# cpu_board.net
KiCad netlist of a schematic drawn in Altium Designer
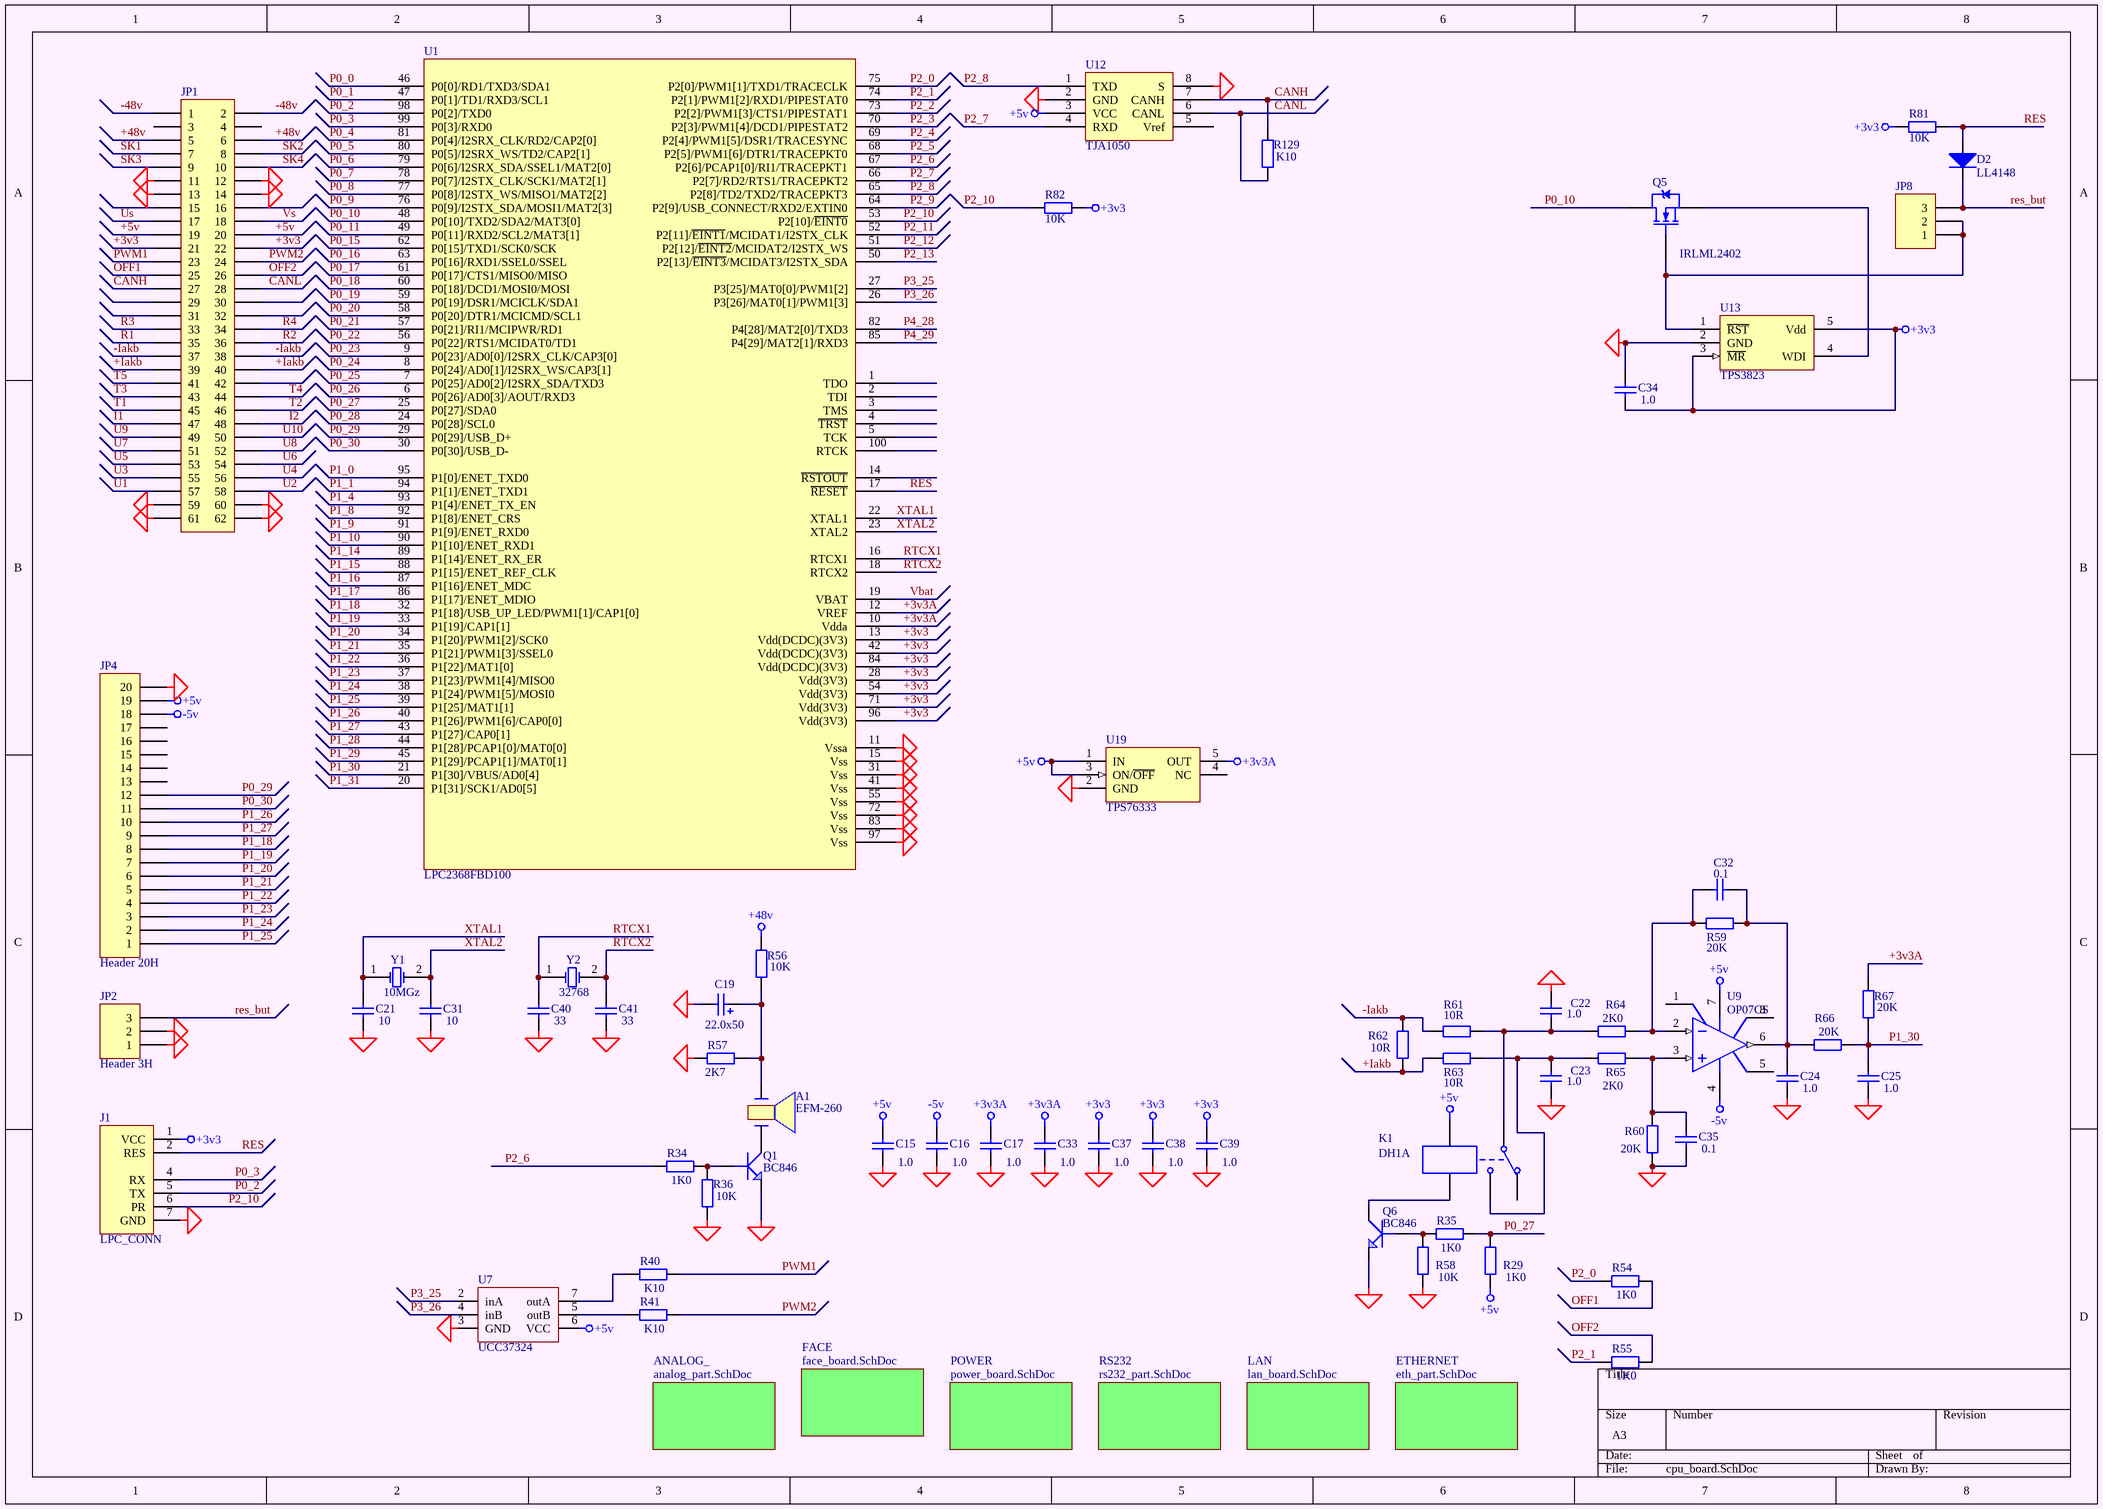
[diagram p0: cpu_board.SchDoc]

(export (version "E")
  (design (tool "Eeschema 10.0.6"))
  (components
    (comp (ref "A1") (value "EFM-260") (footprint "Pjezo15") (libsource (lib "PAL") (part "PJEZ0")))
    (comp (ref "C15")
      (value "1.0")
      (footprint "C3216-1206")
      (description "Capacitor (Semiconductor SIM Model)")
      (fields (field (name "MANUFACTURER") "Generic Components") (field (name "PUBLISHER") "Altium Limited"))
      (libsource (lib "Miscellaneous Devices") (part "Cap Semi"))
    )
    (comp (ref "C16")
      (value "1.0")
      (footprint "C3216-1206")
      (description "Capacitor (Semiconductor SIM Model)")
      (fields (field (name "MANUFACTURER") "Generic Components") (field (name "PUBLISHER") "Altium Limited"))
      (libsource (lib "Miscellaneous Devices") (part "Cap Semi"))
    )
    (comp (ref "C17")
      (value "1.0")
      (footprint "_1206")
      (description "Capacitor (Semiconductor SIM Model)")
      (fields (field (name "MANUFACTURER") "Generic Components") (field (name "PUBLISHER") "Altium Limited"))
      (libsource (lib "Miscellaneous Devices") (part "Cap Semi"))
    )
    (comp (ref "C19")
      (value "22.0x50")
      (footprint "el3")
      (description "Polarized Capacitor (Radial)")
      (fields (field (name "MANUFACTURER") "Generic Components") (field (name "PUBLISHER") "Altium Limited"))
      (libsource (lib "PAL") (part "Cap Pol1"))
    )
    (comp (ref "C21")
      (value "10")
      (footprint "_1206")
      (description "Capacitor (Semiconductor SIM Model)")
      (fields (field (name "MANUFACTURER") "Generic Components") (field (name "PUBLISHER") "Altium Limited"))
      (libsource (lib "Miscellaneous Devices") (part "Cap Semi"))
    )
    (comp (ref "C22")
      (value "1.0")
      (footprint "_1206")
      (description "Capacitor (Semiconductor SIM Model)")
      (fields (field (name "MANUFACTURER") "Generic Components") (field (name "PUBLISHER") "Altium Limited"))
      (libsource (lib "Miscellaneous Devices") (part "Cap Semi"))
    )
    (comp (ref "C23")
      (value "1.0")
      (footprint "_1206")
      (description "Capacitor (Semiconductor SIM Model)")
      (fields (field (name "MANUFACTURER") "Generic Components") (field (name "PUBLISHER") "Altium Limited"))
      (libsource (lib "Miscellaneous Devices") (part "Cap Semi"))
    )
    (comp (ref "C24")
      (value "1.0")
      (footprint "_1206")
      (description "Capacitor (Semiconductor SIM Model)")
      (fields (field (name "MANUFACTURER") "Generic Components") (field (name "PUBLISHER") "Altium Limited"))
      (libsource (lib "Miscellaneous Devices") (part "Cap Semi"))
    )
    (comp (ref "C25")
      (value "1.0")
      (footprint "_1206")
      (description "Capacitor (Semiconductor SIM Model)")
      (fields (field (name "MANUFACTURER") "Generic Components") (field (name "PUBLISHER") "Altium Limited"))
      (libsource (lib "Miscellaneous Devices") (part "Cap Semi"))
    )
    (comp (ref "C31")
      (value "10")
      (footprint "_1206")
      (description "Capacitor (Semiconductor SIM Model)")
      (fields (field (name "MANUFACTURER") "Generic Components") (field (name "PUBLISHER") "Altium Limited"))
      (libsource (lib "Miscellaneous Devices") (part "Cap Semi"))
    )
    (comp (ref "C32")
      (value "0.1")
      (footprint "_1206")
      (description "Capacitor (Semiconductor SIM Model)")
      (fields (field (name "MANUFACTURER") "Generic Components") (field (name "PUBLISHER") "Altium Limited"))
      (libsource (lib "Miscellaneous Devices") (part "Cap Semi"))
    )
    (comp (ref "C33")
      (value "1.0")
      (footprint "_1206")
      (description "Capacitor (Semiconductor SIM Model)")
      (fields (field (name "MANUFACTURER") "Generic Components") (field (name "PUBLISHER") "Altium Limited"))
      (libsource (lib "Miscellaneous Devices") (part "Cap Semi"))
    )
    (comp (ref "C34")
      (value "1.0")
      (footprint "_1206")
      (description "Capacitor")
      (fields (field (name "MANUFACTURER") "Generic Components") (field (name "PUBLISHER") "Altium Limited"))
      (libsource (lib "Miscellaneous Devices") (part "Cap Semi"))
    )
    (comp (ref "C35")
      (value "0.1")
      (footprint "_1206")
      (description "Capacitor (Semiconductor SIM Model)")
      (fields (field (name "MANUFACTURER") "Generic Components") (field (name "PUBLISHER") "Altium Limited"))
      (libsource (lib "Miscellaneous Devices") (part "Cap Semi"))
    )
    (comp (ref "C37")
      (value "1.0")
      (footprint "_1206")
      (description "Capacitor (Semiconductor SIM Model)")
      (fields (field (name "MANUFACTURER") "Generic Components") (field (name "PUBLISHER") "Altium Limited"))
      (libsource (lib "Miscellaneous Devices") (part "Cap Semi"))
    )
    (comp (ref "C38")
      (value "1.0")
      (footprint "_1206")
      (description "Capacitor (Semiconductor SIM Model)")
      (fields (field (name "MANUFACTURER") "Generic Components") (field (name "PUBLISHER") "Altium Limited"))
      (libsource (lib "Miscellaneous Devices") (part "Cap Semi"))
    )
    (comp (ref "C39")
      (value "1.0")
      (footprint "_1206")
      (description "Capacitor (Semiconductor SIM Model)")
      (fields (field (name "MANUFACTURER") "Generic Components") (field (name "PUBLISHER") "Altium Limited"))
      (libsource (lib "Miscellaneous Devices") (part "Cap Semi"))
    )
    (comp (ref "C40")
      (value "33")
      (footprint "_1206")
      (description "Capacitor (Semiconductor SIM Model)")
      (fields (field (name "MANUFACTURER") "Generic Components") (field (name "PUBLISHER") "Altium Limited"))
      (libsource (lib "Miscellaneous Devices") (part "Cap Semi"))
    )
    (comp (ref "C41")
      (value "33")
      (footprint "_1206")
      (description "Capacitor (Semiconductor SIM Model)")
      (fields (field (name "MANUFACTURER") "Generic Components") (field (name "PUBLISHER") "Altium Limited"))
      (libsource (lib "Miscellaneous Devices") (part "Cap Semi"))
    )
    (comp (ref "D2")
      (value "LL4148")
      (footprint "_1206d")
      (description "Default Diode")
      (fields (field (name "MANUFACTURER") "Generic Components") (field (name "PUBLISHER") "Altium Limited"))
      (libsource (lib "PAL") (part "Diode"))
    )
    (comp (ref "J1") (value "LPC_CONN") (footprint "HDR1X7") (libsource (lib "PAL") (part "LPC_CONN")))
    (comp (ref "JP1")
      (value "~")
      (footprint "HDR2X30")
      (description "Header, 30-Pin, Dual row")
      (fields (field (name "MANUFACTURER") "Generic Components") (field (name "PUBLISHER") "Altium Limited"))
      (libsource (lib "UKU205") (part "Header 31X2"))
    )
    (comp (ref "JP2")
      (value "Header 3H")
      (footprint "HDR1X3H")
      (description "Header, 3-Pin,  Right Angle")
      (fields (field (name "MANUFACTURER") "Generic Components") (field (name "PUBLISHER") "Altium Limited"))
      (libsource (lib "Miscellaneous Connectors") (part "Header 3H"))
    )
    (comp (ref "JP4")
      (value "Header 20H")
      (footprint "HDR1X20H")
      (description "Header, 20-Pin,  Right Angle")
      (fields (field (name "MANUFACTURER") "Generic Components") (field (name "PUBLISHER") "Altium Limited"))
      (libsource (lib "Miscellaneous Connectors") (part "Header 20H"))
    )
    (comp (ref "JP8")
      (value "PLS-3")
      (footprint "HDR1X3")
      (description "Header, 3-Pin")
      (fields (field (name "MANUFACTURER") "Generic Components") (field (name "PUBLISHER") "Altium Limited"))
      (libsource (lib "Miscellaneous Connectors") (part "Header 3"))
    )
    (comp (ref "K1")
      (value "DH1A")
      (footprint "kuan")
      (description "Single-Pole Dual-Throw Relay")
      (fields (field (name "MANUFACTURER") "Generic Components") (field (name "PUBLISHER") "Altium Limited"))
      (libsource (lib "PAL") (part "BS115"))
    )
    (comp (ref "Q1") (value "BC846") (footprint "SO-G3") (libsource (lib "MAIN") (part "GT122")))
    (comp (ref "Q5")
      (value "IRLML2402")
      (footprint "SO-G3")
      (description "HEXFET Power MOSFET")
      (fields
        (field (name "MANUFACTURER") "International Rectifier")
        (field (name "PUBLISHER") "Altium Limited")
      )
      (libsource (lib "IR Discrete MOSFET") (part "IRLML2402"))
    )
    (comp (ref "Q6") (value "BC846") (footprint "SO-G3") (libsource (lib "MAIN") (part "GT122")))
    (comp (ref "R29")
      (value "1K0")
      (footprint "_1206")
      (description "Resistor")
      (fields (field (name "MANUFACTURER") "Generic Components") (field (name "PUBLISHER") "Altium Limited"))
      (libsource (lib "") (part "Res2_1"))
    )
    (comp (ref "R34")
      (value "1K0")
      (footprint "_1206")
      (description "Resistor")
      (fields (field (name "MANUFACTURER") "Generic Components") (field (name "PUBLISHER") "Altium Limited"))
      (libsource (lib "") (part "Res2_1"))
    )
    (comp (ref "R35")
      (value "1K0")
      (footprint "_1206")
      (description "Resistor")
      (fields (field (name "MANUFACTURER") "Generic Components") (field (name "PUBLISHER") "Altium Limited"))
      (libsource (lib "") (part "Res2_3"))
    )
    (comp (ref "R36")
      (value "10K")
      (footprint "_1206")
      (description "Resistor")
      (fields (field (name "MANUFACTURER") "Generic Components") (field (name "PUBLISHER") "Altium Limited"))
      (libsource (lib "") (part "Res2_2"))
    )
    (comp (ref "R40")
      (value "K10")
      (footprint "_1206")
      (description "Resistor")
      (fields (field (name "MANUFACTURER") "Generic Components") (field (name "PUBLISHER") "Altium Limited"))
      (libsource (lib "Miscellaneous Devices") (part "Res2"))
    )
    (comp (ref "R41")
      (value "K10")
      (footprint "_1206")
      (description "Resistor")
      (fields (field (name "MANUFACTURER") "Generic Components") (field (name "PUBLISHER") "Altium Limited"))
      (libsource (lib "Miscellaneous Devices") (part "Res2"))
    )
    (comp (ref "R54")
      (value "1K0")
      (footprint "_1206")
      (description "Resistor")
      (fields (field (name "MANUFACTURER") "Generic Components") (field (name "PUBLISHER") "Altium Limited"))
      (libsource (lib "") (part "Res2_1"))
    )
    (comp (ref "R55")
      (value "1K0")
      (footprint "_1206")
      (description "Resistor")
      (fields (field (name "MANUFACTURER") "Generic Components") (field (name "PUBLISHER") "Altium Limited"))
      (libsource (lib "") (part "Res2_1"))
    )
    (comp (ref "R56")
      (value "10K")
      (footprint "_1206")
      (description "Resistor")
      (fields (field (name "MANUFACTURER") "Generic Components") (field (name "PUBLISHER") "Altium Limited"))
      (libsource (lib "") (part "Res2_2"))
    )
    (comp (ref "R57")
      (value "2K7")
      (footprint "_1206")
      (description "Resistor")
      (fields (field (name "MANUFACTURER") "Generic Components") (field (name "PUBLISHER") "Altium Limited"))
      (libsource (lib "") (part "Res2_1"))
    )
    (comp (ref "R58")
      (value "10K")
      (footprint "_1206")
      (description "Resistor")
      (fields (field (name "MANUFACTURER") "Generic Components") (field (name "PUBLISHER") "Altium Limited"))
      (libsource (lib "") (part "Res2_1"))
    )
    (comp (ref "R59")
      (value "20K")
      (footprint "_1206")
      (description "Resistor")
      (fields (field (name "MANUFACTURER") "Generic Components") (field (name "PUBLISHER") "Altium Limited"))
      (libsource (lib "Miscellaneous Devices") (part "Res2"))
    )
    (comp (ref "R60")
      (value "20K")
      (footprint "_1206")
      (description "Resistor")
      (fields (field (name "MANUFACTURER") "Generic Components") (field (name "PUBLISHER") "Altium Limited"))
      (libsource (lib "") (part "Res2_2"))
    )
    (comp (ref "R61")
      (value "10R")
      (footprint "_1206")
      (description "Resistor")
      (fields (field (name "MANUFACTURER") "Generic Components") (field (name "PUBLISHER") "Altium Limited"))
      (libsource (lib "Miscellaneous Devices") (part "Res2"))
    )
    (comp (ref "R62")
      (value "10R")
      (footprint "_1206")
      (description "Resistor")
      (fields (field (name "MANUFACTURER") "Generic Components") (field (name "PUBLISHER") "Altium Limited"))
      (libsource (lib "") (part "Res2_2"))
    )
    (comp (ref "R63")
      (value "10R")
      (footprint "_1206")
      (description "Resistor")
      (fields (field (name "MANUFACTURER") "Generic Components") (field (name "PUBLISHER") "Altium Limited"))
      (libsource (lib "Miscellaneous Devices") (part "Res2"))
    )
    (comp (ref "R64")
      (value "2K0")
      (footprint "_1206")
      (description "Resistor")
      (fields (field (name "MANUFACTURER") "Generic Components") (field (name "PUBLISHER") "Altium Limited"))
      (libsource (lib "") (part "Res2_1"))
    )
    (comp (ref "R65")
      (value "2K0")
      (footprint "_1206")
      (description "Resistor")
      (fields (field (name "MANUFACTURER") "Generic Components") (field (name "PUBLISHER") "Altium Limited"))
      (libsource (lib "") (part "Res2_1"))
    )
    (comp (ref "R66")
      (value "20K")
      (footprint "_1206")
      (description "Resistor")
      (fields (field (name "MANUFACTURER") "Generic Components") (field (name "PUBLISHER") "Altium Limited"))
      (libsource (lib "") (part "Res2_1"))
    )
    (comp (ref "R67")
      (value "20K")
      (footprint "_1206")
      (description "Resistor")
      (fields (field (name "MANUFACTURER") "Generic Components") (field (name "PUBLISHER") "Altium Limited"))
      (libsource (lib "") (part "Res2_1"))
    )
    (comp (ref "R81")
      (value "10K")
      (footprint "_1206")
      (description "Resistor")
      (fields (field (name "MANUFACTURER") "Generic Components") (field (name "PUBLISHER") "Altium Limited"))
      (libsource (lib "Miscellaneous Devices") (part "Res2"))
    )
    (comp (ref "R82")
      (value "10K")
      (footprint "_1206")
      (description "Resistor")
      (fields (field (name "MANUFACTURER") "Generic Components") (field (name "PUBLISHER") "Altium Limited"))
      (libsource (lib "Miscellaneous Devices") (part "Res2"))
    )
    (comp (ref "R129")
      (value "K10")
      (footprint "_1206")
      (description "Resistor")
      (fields (field (name "MANUFACTURER") "Generic Components") (field (name "PUBLISHER") "Altium Limited"))
      (libsource (lib "") (part "Res2_2"))
    )
    (comp (ref "U1")
      (value "LPC2368FBD100")
      (footprint "LPC2368")
      (libsource (lib "PAL") (part "LPC2368FBD100"))
    )
    (comp (ref "U7") (value "UCC37324") (footprint "SO-G8") (libsource (lib "PAL") (part "UCC37324")))
    (comp (ref "U9")
      (value "OP07CS")
      (footprint "SO-G8")
      (description "Ultra-Low Offset Voltage Operational Amplifier")
      (fields (field (name "MANUFACTURER") "Analog Devices") (field (name "PUBLISHER") "Altium Limited"))
      (libsource (lib "AD Operational Amplifier") (part "OP07CS"))
    )
    (comp (ref "U12") (value "TJA1050") (footprint "SO-G8") (libsource (lib "PAL") (part "TJA1050")))
    (comp (ref "U13")
      (value "TPS3823")
      (footprint "SO-G5/P.95")
      (description "Reset IC")
      (fields
        (field (name "MANUFACTURER") "National Semiconductor")
        (field (name "PUBLISHER") "Altium Limited")
      )
      (libsource (lib "PAL") (part "TPS3823"))
    )
    (comp (ref "U19")
      (value "TPS76333")
      (footprint "SO-G5/P.95")
      (description "Micropower SOT, 50 mA Ultra Low-Dropout Regulator")
      (fields
        (field (name "MANUFACTURER") "National Semiconductor")
        (field (name "PUBLISHER") "Altium Limited")
      )
      (libsource (lib "NSC Power Mgt Voltage Regulator") (part "LP2980AIM5-3.3"))
    )
    (comp (ref "Y1")
      (value "10MGz")
      (footprint "QWARZ1")
      (description "Crystal Oscillator")
      (fields (field (name "MANUFACTURER") "Generic Components") (field (name "PUBLISHER") "Altium Limited"))
      (libsource (lib "Miscellaneous Devices") (part "XTAL"))
    )
    (comp (ref "Y2")
      (value "32768")
      (footprint "QWARZ2")
      (description "Crystal Oscillator")
      (fields (field (name "MANUFACTURER") "Generic Components") (field (name "PUBLISHER") "Altium Limited"))
      (libsource (lib "") (part "XTAL_1"))
    )
  )
  (nets
    (net (code "1") (name "+3v3") (class "Default")
      (node (ref "C34") (pin "1") (pinfunction "1_1") (pintype "passive"))
      (node (ref "C37") (pin "2") (pinfunction "2_2") (pintype "passive"))
      (node (ref "C38") (pin "2") (pinfunction "2_2") (pintype "passive"))
      (node (ref "C39") (pin "2") (pinfunction "2_2") (pintype "passive"))
      (node (ref "J1") (pin "1") (pinfunction "VCC_1") (pintype "passive"))
      (node (ref "JP1") (pin "21") (pinfunction "21_21") (pintype "passive"))
      (node (ref "JP1") (pin "22") (pinfunction "22_22") (pintype "passive"))
      (node (ref "R81") (pin "2") (pinfunction "2_2") (pintype "passive"))
      (node (ref "R82") (pin "1") (pinfunction "1_1") (pintype "passive"))
      (node (ref "U1") (pin "13") (pinfunction "Vdd(DCDC)(3V3)_13") (pintype "passive"))
      (node (ref "U1") (pin "28") (pinfunction "Vdd(3V3)_28") (pintype "passive"))
      (node (ref "U1") (pin "42") (pinfunction "Vdd(DCDC)(3V3)_42") (pintype "passive"))
      (node (ref "U1") (pin "54") (pinfunction "Vdd(3V3)_54") (pintype "passive"))
      (node (ref "U1") (pin "71") (pinfunction "Vdd(3V3)_71") (pintype "passive"))
      (node (ref "U1") (pin "84") (pinfunction "Vdd(DCDC)(3V3)_84") (pintype "passive"))
      (node (ref "U1") (pin "96") (pinfunction "Vdd(3V3)_96") (pintype "passive"))
      (node (ref "U13") (pin "3") (pinfunction "~{MR}_3") (pintype "input"))
      (node (ref "U13") (pin "5") (pinfunction "Vdd_5") (pintype "power_in"))
    )
    (net (code "2") (name "+3v3A") (class "Default")
      (node (ref "C17") (pin "2") (pinfunction "2_2") (pintype "passive"))
      (node (ref "C33") (pin "2") (pinfunction "2_2") (pintype "passive"))
      (node (ref "R67") (pin "2") (pinfunction "2_2") (pintype "passive"))
      (node (ref "U1") (pin "10") (pinfunction "Vdda_10") (pintype "passive"))
      (node (ref "U1") (pin "12") (pinfunction "VREF_12") (pintype "passive"))
      (node (ref "U19") (pin "5") (pinfunction "OUT_5") (pintype "power_in"))
    )
    (net (code "3") (name "+5v") (class "Default")
      (node (ref "C15") (pin "2") (pinfunction "2_2") (pintype "passive"))
      (node (ref "JP1") (pin "19") (pinfunction "19_19") (pintype "passive"))
      (node (ref "JP1") (pin "20") (pinfunction "20_20") (pintype "passive"))
      (node (ref "JP4") (pin "19") (pinfunction "19_19") (pintype "passive"))
      (node (ref "K1") (pin "4") (pinfunction "4_4") (pintype "passive"))
      (node (ref "R29") (pin "1") (pinfunction "1_1") (pintype "passive"))
      (node (ref "U12") (pin "3") (pinfunction "VCC_3") (pintype "passive"))
      (node (ref "U19") (pin "1") (pinfunction "IN_1") (pintype "power_in"))
      (node (ref "U19") (pin "3") (pinfunction "ON/~{OFF}_3") (pintype "input"))
      (node (ref "U7") (pin "6") (pinfunction "VCC_6") (pintype "passive"))
      (node (ref "U9") (pin "7") (pinfunction "V+_7") (pintype "power_in"))
    )
    (net (code "4") (name "+48v") (class "Default")
      (node (ref "JP1") (pin "5") (pinfunction "5_5") (pintype "passive"))
      (node (ref "JP1") (pin "6") (pinfunction "6_6") (pintype "passive"))
      (node (ref "R56") (pin "2") (pinfunction "2_2") (pintype "passive"))
    )
    (net (code "5") (name "-5v") (class "Default")
      (node (ref "C16") (pin "2") (pinfunction "2_2") (pintype "passive"))
      (node (ref "JP4") (pin "18") (pinfunction "18_18") (pintype "passive"))
      (node (ref "U9") (pin "4") (pinfunction "V-_4") (pintype "power_in"))
    )
    (net (code "6") (name "/+Iakb") (class "Default")
      (node (ref "JP1") (pin "39") (pinfunction "39_39") (pintype "passive"))
      (node (ref "JP1") (pin "40") (pinfunction "40_40") (pintype "passive"))
      (node (ref "R62") (pin "1") (pinfunction "1_1") (pintype "passive"))
      (node (ref "R63") (pin "2") (pinfunction "2_2") (pintype "passive"))
    )
    (net (code "7") (name "/-48v") (class "Default")
      (node (ref "JP1") (pin "1") (pinfunction "1_1") (pintype "passive"))
      (node (ref "JP1") (pin "2") (pinfunction "2_2") (pintype "passive"))
    )
    (net (code "8") (name "/-Iakb") (class "Default")
      (node (ref "JP1") (pin "37") (pinfunction "37_37") (pintype "passive"))
      (node (ref "JP1") (pin "38") (pinfunction "38_38") (pintype "passive"))
      (node (ref "R61") (pin "2") (pinfunction "2_2") (pintype "passive"))
      (node (ref "R62") (pin "2") (pinfunction "2_2") (pintype "passive"))
    )
    (net (code "10") (name "/CANH") (class "Default")
      (node (ref "JP1") (pin "27") (pinfunction "27_27") (pintype "passive"))
      (node (ref "R129") (pin "2") (pinfunction "2_2") (pintype "passive"))
      (node (ref "U12") (pin "7") (pinfunction "CANH_7") (pintype "passive"))
    )
    (net (code "11") (name "/CANL") (class "Default")
      (node (ref "JP1") (pin "28") (pinfunction "28_28") (pintype "passive"))
      (node (ref "R129") (pin "1") (pinfunction "1_1") (pintype "passive"))
      (node (ref "U12") (pin "6") (pinfunction "CANL_6") (pintype "passive"))
    )
    (net (code "12") (name "/I1") (class "Default")
      (node (ref "JP1") (pin "47") (pinfunction "47_47") (pintype "passive"))
    )
    (net (code "13") (name "/I2") (class "Default")
      (node (ref "JP1") (pin "48") (pinfunction "48_48") (pintype "passive"))
    )
    (net (code "14") (name "/OFF1") (class "Default")
      (node (ref "JP1") (pin "25") (pinfunction "25_25") (pintype "passive"))
      (node (ref "R54") (pin "2") (pinfunction "2_2") (pintype "passive"))
    )
    (net (code "15") (name "/OFF2") (class "Default")
      (node (ref "JP1") (pin "26") (pinfunction "26_26") (pintype "passive"))
      (node (ref "R55") (pin "2") (pinfunction "2_2") (pintype "passive"))
    )
    (net (code "16") (name "/P0_0") (class "Default")
      (node (ref "U1") (pin "46") (pinfunction "P0[0]/RD1/TXD3/SDA1_46") (pintype "passive"))
    )
    (net (code "17") (name "/P0_1") (class "Default")
      (node (ref "U1") (pin "47") (pinfunction "P0[1]/TD1/RXD3/SCL1_47") (pintype "passive"))
    )
    (net (code "18") (name "/P0_2") (class "Default")
      (node (ref "J1") (pin "5") (pinfunction "TX_5") (pintype "passive"))
      (node (ref "U1") (pin "98") (pinfunction "P0[2]/TXD0_98") (pintype "passive"))
    )
    (net (code "19") (name "/P0_3") (class "Default")
      (node (ref "J1") (pin "4") (pinfunction "RX_4") (pintype "passive"))
      (node (ref "U1") (pin "99") (pinfunction "P0[3]/RXD0_99") (pintype "passive"))
    )
    (net (code "20") (name "/P0_4") (class "Default")
      (node (ref "U1") (pin "81") (pinfunction "P0[4]/I2SRX_CLK/RD2/CAP2[0]_81") (pintype "passive"))
    )
    (net (code "21") (name "/P0_5") (class "Default")
      (node (ref "U1") (pin "80") (pinfunction "P0[5]/I2SRX_WS/TD2/CAP2[1]_80") (pintype "passive"))
    )
    (net (code "22") (name "/P0_6") (class "Default")
      (node (ref "U1") (pin "79") (pinfunction "P0[6]/I2SRX_SDA/SSEL1/MAT2[0]_79") (pintype "passive"))
    )
    (net (code "23") (name "/P0_7") (class "Default")
      (node (ref "U1") (pin "78") (pinfunction "P0[7]/I2STX_CLK/SCK1/MAT2[1]_78") (pintype "passive"))
    )
    (net (code "24") (name "/P0_8") (class "Default")
      (node (ref "U1") (pin "77") (pinfunction "P0[8]/I2STX_WS/MISO1/MAT2[2]_77") (pintype "passive"))
    )
    (net (code "25") (name "/P0_9") (class "Default")
      (node (ref "U1") (pin "76") (pinfunction "P0[9]/I2STX_SDA/MOSI1/MAT2[3]_76") (pintype "passive"))
    )
    (net (code "26") (name "/P0_10") (class "Default")
      (node (ref "Q5") (pin "3") (pinfunction "D_3") (pintype "passive"))
      (node (ref "U1") (pin "48") (pinfunction "P0[10]/TXD2/SDA2/MAT3[0]_48") (pintype "passive"))
    )
    (net (code "27") (name "/P0_11") (class "Default")
      (node (ref "U1") (pin "49") (pinfunction "P0[11]/RXD2/SCL2/MAT3[1]_49") (pintype "passive"))
    )
    (net (code "28") (name "/P0_15") (class "Default")
      (node (ref "U1") (pin "62") (pinfunction "P0[15]/TXD1/SCK0/SCK_62") (pintype "passive"))
    )
    (net (code "29") (name "/P0_16") (class "Default")
      (node (ref "U1") (pin "63") (pinfunction "P0[16]/RXD1/SSEL0/SSEL_63") (pintype "passive"))
    )
    (net (code "30") (name "/P0_17") (class "Default")
      (node (ref "U1") (pin "61") (pinfunction "P0[17]/CTS1/MISO0/MISO_61") (pintype "passive"))
    )
    (net (code "31") (name "/P0_18") (class "Default")
      (node (ref "U1") (pin "60") (pinfunction "P0[18]/DCD1/MOSI0/MOSI_60") (pintype "passive"))
    )
    (net (code "32") (name "/P0_19") (class "Default")
      (node (ref "U1") (pin "59") (pinfunction "P0[19]/DSR1/MCICLK/SDA1_59") (pintype "passive"))
    )
    (net (code "33") (name "/P0_20") (class "Default")
      (node (ref "U1") (pin "58") (pinfunction "P0[20]/DTR1/MCICMD/SCL1_58") (pintype "passive"))
    )
    (net (code "34") (name "/P0_21") (class "Default")
      (node (ref "U1") (pin "57") (pinfunction "P0[21]/RI1/MCIPWR/RD1_57") (pintype "passive"))
    )
    (net (code "35") (name "/P0_22") (class "Default")
      (node (ref "U1") (pin "56") (pinfunction "P0[22]/RTS1/MCIDAT0/TD1_56") (pintype "passive"))
    )
    (net (code "36") (name "/P0_23") (class "Default")
      (node (ref "U1") (pin "9") (pinfunction "P0[23]/AD0[0]/I2SRX_CLK/CAP3[0]_9") (pintype "passive"))
    )
    (net (code "37") (name "/P0_24") (class "Default")
      (node (ref "U1") (pin "8") (pinfunction "P0[24]/AD0[1]/I2SRX_WS/CAP3[1]_8") (pintype "passive"))
    )
    (net (code "38") (name "/P0_25") (class "Default")
      (node (ref "U1") (pin "7") (pinfunction "P0[25]/AD0[2]/I2SRX_SDA/TXD3_7") (pintype "passive"))
    )
    (net (code "39") (name "/P0_26") (class "Default")
      (node (ref "U1") (pin "6") (pinfunction "P0[26]/AD0[3]/AOUT/RXD3_6") (pintype "passive"))
    )
    (net (code "40") (name "/P0_27") (class "Default")
      (node (ref "R29") (pin "2") (pinfunction "2_2") (pintype "passive"))
      (node (ref "R35") (pin "1") (pinfunction "1_1") (pintype "passive"))
      (node (ref "U1") (pin "25") (pinfunction "P0[27]/SDA0_25") (pintype "passive"))
    )
    (net (code "41") (name "/P0_28") (class "Default")
      (node (ref "U1") (pin "24") (pinfunction "P0[28]/SCL0_24") (pintype "passive"))
    )
    (net (code "42") (name "/P0_29") (class "Default")
      (node (ref "JP4") (pin "12") (pinfunction "12_12") (pintype "passive"))
      (node (ref "U1") (pin "29") (pinfunction "P0[29]/USB_D+_29") (pintype "passive"))
    )
    (net (code "43") (name "/P0_30") (class "Default")
      (node (ref "JP4") (pin "11") (pinfunction "11_11") (pintype "passive"))
      (node (ref "U1") (pin "30") (pinfunction "P0[30]/USB_D-_30") (pintype "passive"))
    )
    (net (code "44") (name "/P1_0") (class "Default")
      (node (ref "U1") (pin "95") (pinfunction "P1[0]/ENET_TXD0_95") (pintype "passive"))
    )
    (net (code "45") (name "/P1_1") (class "Default")
      (node (ref "U1") (pin "94") (pinfunction "P1[1]/ENET_TXD1_94") (pintype "passive"))
    )
    (net (code "46") (name "/P1_4") (class "Default")
      (node (ref "U1") (pin "93") (pinfunction "P1[4]/ENET_TX_EN_93") (pintype "passive"))
    )
    (net (code "47") (name "/P1_8") (class "Default")
      (node (ref "U1") (pin "92") (pinfunction "P1[8]/ENET_CRS_92") (pintype "passive"))
    )
    (net (code "48") (name "/P1_9") (class "Default")
      (node (ref "U1") (pin "91") (pinfunction "P1[9]/ENET_RXD0_91") (pintype "passive"))
    )
    (net (code "49") (name "/P1_10") (class "Default")
      (node (ref "U1") (pin "90") (pinfunction "P1[10]/ENET_RXD1_90") (pintype "passive"))
    )
    (net (code "50") (name "/P1_14") (class "Default")
      (node (ref "U1") (pin "89") (pinfunction "P1[14]/ENET_RX_ER_89") (pintype "passive"))
    )
    (net (code "51") (name "/P1_15") (class "Default")
      (node (ref "U1") (pin "88") (pinfunction "P1[15]/ENET_REF_CLK_88") (pintype "passive"))
    )
    (net (code "52") (name "/P1_16") (class "Default")
      (node (ref "U1") (pin "87") (pinfunction "P1[16]/ENET_MDC_87") (pintype "passive"))
    )
    (net (code "53") (name "/P1_17") (class "Default")
      (node (ref "U1") (pin "86") (pinfunction "P1[17]/ENET_MDIO_86") (pintype "passive"))
    )
    (net (code "54") (name "/P1_18") (class "Default")
      (node (ref "JP4") (pin "8") (pinfunction "8_8") (pintype "passive"))
      (node (ref "U1") (pin "32") (pinfunction "P1[18]/USB_UP_LED/PWM1[1]/CAP1[0]_32") (pintype "passive"))
    )
    (net (code "55") (name "/P1_19") (class "Default")
      (node (ref "JP4") (pin "7") (pinfunction "7_7") (pintype "passive"))
      (node (ref "U1") (pin "33") (pinfunction "P1[19]/CAP1[1]_33") (pintype "passive"))
    )
    (net (code "56") (name "/P1_20") (class "Default")
      (node (ref "JP4") (pin "6") (pinfunction "6_6") (pintype "passive"))
      (node (ref "U1") (pin "34") (pinfunction "P1[20]/PWM1[2]/SCK0_34") (pintype "passive"))
    )
    (net (code "57") (name "/P1_21") (class "Default")
      (node (ref "JP4") (pin "5") (pinfunction "5_5") (pintype "passive"))
      (node (ref "U1") (pin "35") (pinfunction "P1[21]/PWM1[3]/SSEL0_35") (pintype "passive"))
    )
    (net (code "58") (name "/P1_22") (class "Default")
      (node (ref "JP4") (pin "4") (pinfunction "4_4") (pintype "passive"))
      (node (ref "U1") (pin "36") (pinfunction "P1[22]/MAT1[0]_36") (pintype "passive"))
    )
    (net (code "59") (name "/P1_23") (class "Default")
      (node (ref "JP4") (pin "3") (pinfunction "3_3") (pintype "passive"))
      (node (ref "U1") (pin "37") (pinfunction "P1[23]/PWM1[4]/MISO0_37") (pintype "passive"))
    )
    (net (code "60") (name "/P1_24") (class "Default")
      (node (ref "JP4") (pin "2") (pinfunction "2_2") (pintype "passive"))
      (node (ref "U1") (pin "38") (pinfunction "P1[24]/PWM1[5]/MOSI0_38") (pintype "passive"))
    )
    (net (code "61") (name "/P1_25") (class "Default")
      (node (ref "JP4") (pin "1") (pinfunction "1_1") (pintype "passive"))
      (node (ref "U1") (pin "39") (pinfunction "P1[25]/MAT1[1]_39") (pintype "passive"))
    )
    (net (code "62") (name "/P1_26") (class "Default")
      (node (ref "JP4") (pin "10") (pinfunction "10_10") (pintype "passive"))
      (node (ref "U1") (pin "40") (pinfunction "P1[26]/PWM1[6]/CAP0[0]_40") (pintype "passive"))
    )
    (net (code "63") (name "/P1_27") (class "Default")
      (node (ref "JP4") (pin "9") (pinfunction "9_9") (pintype "passive"))
      (node (ref "U1") (pin "43") (pinfunction "P1[27]/CAP0[1]_43") (pintype "passive"))
    )
    (net (code "64") (name "/P1_28") (class "Default")
      (node (ref "U1") (pin "44") (pinfunction "P1[28]/PCAP1[0]/MAT0[0]_44") (pintype "passive"))
    )
    (net (code "65") (name "/P1_29") (class "Default")
      (node (ref "U1") (pin "45") (pinfunction "P1[29]/PCAP1[1]/MAT0[1]_45") (pintype "passive"))
    )
    (net (code "66") (name "/P1_30") (class "Default")
      (node (ref "C25") (pin "2") (pinfunction "2_2") (pintype "passive"))
      (node (ref "R66") (pin "2") (pinfunction "2_2") (pintype "passive"))
      (node (ref "R67") (pin "1") (pinfunction "1_1") (pintype "passive"))
      (node (ref "U1") (pin "21") (pinfunction "P1[30]/VBUS/AD0[4]_21") (pintype "passive"))
    )
    (net (code "67") (name "/P1_31") (class "Default")
      (node (ref "U1") (pin "20") (pinfunction "P1[31]/SCK1/AD0[5]_20") (pintype "passive"))
    )
    (net (code "68") (name "/P2_0") (class "Default")
      (node (ref "R54") (pin "1") (pinfunction "1_1") (pintype "passive"))
      (node (ref "U1") (pin "75") (pinfunction "P2[0]/PWM1[1]/TXD1/TRACECLK_75") (pintype "passive"))
    )
    (net (code "69") (name "/P2_1") (class "Default")
      (node (ref "R55") (pin "1") (pinfunction "1_1") (pintype "passive"))
      (node (ref "U1") (pin "74") (pinfunction "P2[1]/PWM1[2]/RXD1/PIPESTAT0_74") (pintype "passive"))
    )
    (net (code "70") (name "/P2_2") (class "Default")
      (node (ref "U1") (pin "73") (pinfunction "P2[2]/PWM1[3]/CTS1/PIPESTAT1_73") (pintype "passive"))
    )
    (net (code "71") (name "/P2_3") (class "Default")
      (node (ref "U1") (pin "70") (pinfunction "P2[3]/PWM1[4]/DCD1/PIPESTAT2_70") (pintype "passive"))
    )
    (net (code "72") (name "/P2_4") (class "Default")
      (node (ref "U1") (pin "69") (pinfunction "P2[4]/PWM1[5]/DSR1/TRACESYNC_69") (pintype "passive"))
    )
    (net (code "73") (name "/P2_5") (class "Default")
      (node (ref "U1") (pin "68") (pinfunction "P2[5]/PWM1[6]/DTR1/TRACEPKT0_68") (pintype "passive"))
    )
    (net (code "74") (name "/P2_6") (class "Default")
      (node (ref "R34") (pin "1") (pinfunction "1_1") (pintype "passive"))
      (node (ref "U1") (pin "67") (pinfunction "P2[6]/PCAP1[0]/RI1/TRACEPKT1_67") (pintype "passive"))
    )
    (net (code "75") (name "/P2_7") (class "Default")
      (node (ref "U1") (pin "66") (pinfunction "P2[7]/RD2/RTS1/TRACEPKT2_66") (pintype "passive"))
      (node (ref "U12") (pin "4") (pinfunction "RXD_4") (pintype "passive"))
    )
    (net (code "76") (name "/P2_8") (class "Default")
      (node (ref "U1") (pin "65") (pinfunction "P2[8]/TD2/TXD2/TRACEPKT3_65") (pintype "passive"))
      (node (ref "U12") (pin "1") (pinfunction "TXD_1") (pintype "passive"))
    )
    (net (code "77") (name "/P2_9") (class "Default")
      (node (ref "U1") (pin "64") (pinfunction "P2[9]/USB_CONNECT/RXD2/EXTIN0_64") (pintype "passive"))
    )
    (net (code "78") (name "/P2_10") (class "Default")
      (node (ref "J1") (pin "6") (pinfunction "PR_6") (pintype "passive"))
      (node (ref "R82") (pin "2") (pinfunction "2_2") (pintype "passive"))
      (node (ref "U1") (pin "53") (pinfunction "P2[10]/~{EINT0}_53") (pintype "passive"))
    )
    (net (code "79") (name "/P2_11") (class "Default")
      (node (ref "U1") (pin "52") (pinfunction "P2[11]/~{EINT1}/MCIDAT1/I2STX_CLK_52") (pintype "passive"))
    )
    (net (code "80") (name "/P2_12") (class "Default")
      (node (ref "U1") (pin "51") (pinfunction "P2[12]/~{EINT2}/MCIDAT2/I2STX_WS_51") (pintype "passive"))
    )
    (net (code "81") (name "/P2_13") (class "Default")
      (node (ref "U1") (pin "50") (pinfunction "P2[13]/~{EINT3}/MCIDAT3/I2STX_SDA_50") (pintype "passive"))
    )
    (net (code "82") (name "/P3_25") (class "Default")
      (node (ref "U1") (pin "27") (pinfunction "P3[25]/MAT0[0]/PWM1[2]_27") (pintype "passive"))
      (node (ref "U7") (pin "2") (pinfunction "inA_2") (pintype "passive"))
    )
    (net (code "83") (name "/P3_26") (class "Default")
      (node (ref "U1") (pin "26") (pinfunction "P3[26]/MAT0[1]/PWM1[3]_26") (pintype "passive"))
      (node (ref "U7") (pin "4") (pinfunction "inB_4") (pintype "passive"))
    )
    (net (code "84") (name "/P4_28") (class "Default")
      (node (ref "U1") (pin "82") (pinfunction "P4[28]/MAT2[0]/TXD3_82") (pintype "passive"))
    )
    (net (code "85") (name "/P4_29") (class "Default")
      (node (ref "U1") (pin "85") (pinfunction "P4[29]/MAT2[1]/RXD3_85") (pintype "passive"))
    )
    (net (code "86") (name "/PWM1") (class "Default")
      (node (ref "JP1") (pin "23") (pinfunction "23_23") (pintype "passive"))
      (node (ref "R40") (pin "1") (pinfunction "1_1") (pintype "passive"))
    )
    (net (code "87") (name "/PWM2") (class "Default")
      (node (ref "JP1") (pin "24") (pinfunction "24_24") (pintype "passive"))
      (node (ref "R41") (pin "1") (pinfunction "1_1") (pintype "passive"))
    )
    (net (code "88") (name "/R1") (class "Default")
      (node (ref "JP1") (pin "35") (pinfunction "35_35") (pintype "passive"))
    )
    (net (code "89") (name "/R2") (class "Default")
      (node (ref "JP1") (pin "36") (pinfunction "36_36") (pintype "passive"))
    )
    (net (code "90") (name "/R3") (class "Default")
      (node (ref "JP1") (pin "33") (pinfunction "33_33") (pintype "passive"))
    )
    (net (code "91") (name "/R4") (class "Default")
      (node (ref "JP1") (pin "34") (pinfunction "34_34") (pintype "passive"))
    )
    (net (code "92") (name "/RES") (class "Default")
      (node (ref "D2") (pin "1") (pinfunction "A_1") (pintype "passive"))
      (node (ref "J1") (pin "2") (pinfunction "RES_2") (pintype "passive"))
      (node (ref "R81") (pin "1") (pinfunction "1_1") (pintype "passive"))
      (node (ref "U1") (pin "17") (pinfunction "~{RESET}_17") (pintype "passive"))
    )
    (net (code "93") (name "/RTCX1") (class "Default")
      (node (ref "C40") (pin "2") (pinfunction "2_2") (pintype "passive"))
      (node (ref "U1") (pin "16") (pinfunction "RTCX1_16") (pintype "passive"))
      (node (ref "Y2") (pin "1") (pinfunction "OSC1_1") (pintype "passive"))
    )
    (net (code "94") (name "/RTCX2") (class "Default")
      (node (ref "C41") (pin "2") (pinfunction "2_2") (pintype "passive"))
      (node (ref "U1") (pin "18") (pinfunction "RTCX2_18") (pintype "passive"))
      (node (ref "Y2") (pin "2") (pinfunction "OSC2_2") (pintype "passive"))
    )
    (net (code "95") (name "/SK1") (class "Default")
      (node (ref "JP1") (pin "7") (pinfunction "7_7") (pintype "passive"))
    )
    (net (code "96") (name "/SK2") (class "Default")
      (node (ref "JP1") (pin "8") (pinfunction "8_8") (pintype "passive"))
    )
    (net (code "97") (name "/SK3") (class "Default")
      (node (ref "JP1") (pin "9") (pinfunction "9_9") (pintype "passive"))
    )
    (net (code "98") (name "/SK4") (class "Default")
      (node (ref "JP1") (pin "10") (pinfunction "10_10") (pintype "passive"))
    )
    (net (code "99") (name "/T1") (class "Default")
      (node (ref "JP1") (pin "45") (pinfunction "45_45") (pintype "passive"))
    )
    (net (code "100") (name "/T2") (class "Default")
      (node (ref "JP1") (pin "46") (pinfunction "46_46") (pintype "passive"))
    )
    (net (code "101") (name "/T3") (class "Default")
      (node (ref "JP1") (pin "43") (pinfunction "43_43") (pintype "passive"))
    )
    (net (code "102") (name "/T4") (class "Default")
      (node (ref "JP1") (pin "44") (pinfunction "44_44") (pintype "passive"))
    )
    (net (code "103") (name "/T5") (class "Default")
      (node (ref "JP1") (pin "41") (pinfunction "41_41") (pintype "passive"))
    )
    (net (code "104") (name "/U1") (class "Default")
      (node (ref "JP1") (pin "57") (pinfunction "57_57") (pintype "passive"))
    )
    (net (code "105") (name "/U2") (class "Default")
      (node (ref "JP1") (pin "58") (pinfunction "58_58") (pintype "passive"))
    )
    (net (code "106") (name "/U3") (class "Default")
      (node (ref "JP1") (pin "55") (pinfunction "55_55") (pintype "passive"))
    )
    (net (code "107") (name "/U4") (class "Default")
      (node (ref "JP1") (pin "56") (pinfunction "56_56") (pintype "passive"))
    )
    (net (code "108") (name "/U5") (class "Default")
      (node (ref "JP1") (pin "53") (pinfunction "53_53") (pintype "passive"))
    )
    (net (code "109") (name "/U6") (class "Default")
      (node (ref "JP1") (pin "54") (pinfunction "54_54") (pintype "passive"))
    )
    (net (code "110") (name "/U7") (class "Default")
      (node (ref "JP1") (pin "51") (pinfunction "51_51") (pintype "passive"))
    )
    (net (code "111") (name "/U8") (class "Default")
      (node (ref "JP1") (pin "52") (pinfunction "52_52") (pintype "passive"))
    )
    (net (code "112") (name "/U9") (class "Default")
      (node (ref "JP1") (pin "49") (pinfunction "49_49") (pintype "passive"))
    )
    (net (code "113") (name "/U10") (class "Default")
      (node (ref "JP1") (pin "50") (pinfunction "50_50") (pintype "passive"))
    )
    (net (code "114") (name "/Us") (class "Default")
      (node (ref "JP1") (pin "17") (pinfunction "17_17") (pintype "passive"))
    )
    (net (code "115") (name "/Vbat") (class "Default")
      (node (ref "U1") (pin "19") (pinfunction "VBAT_19") (pintype "passive"))
    )
    (net (code "116") (name "/Vs") (class "Default")
      (node (ref "JP1") (pin "18") (pinfunction "18_18") (pintype "passive"))
    )
    (net (code "117") (name "/XTAL1") (class "Default")
      (node (ref "C21") (pin "2") (pinfunction "2_2") (pintype "passive"))
      (node (ref "U1") (pin "22") (pinfunction "XTAL1_22") (pintype "passive"))
      (node (ref "Y1") (pin "1") (pinfunction "OSC1_1") (pintype "passive"))
    )
    (net (code "118") (name "/XTAL2") (class "Default")
      (node (ref "C31") (pin "2") (pinfunction "2_2") (pintype "passive"))
      (node (ref "U1") (pin "23") (pinfunction "XTAL2_23") (pintype "passive"))
      (node (ref "Y1") (pin "2") (pinfunction "OSC2_2") (pintype "passive"))
    )
    (net (code "119") (name "/res_but") (class "Default")
      (node (ref "D2") (pin "2") (pinfunction "K_2") (pintype "passive"))
      (node (ref "JP2") (pin "3") (pinfunction "3_3") (pintype "passive"))
      (node (ref "JP8") (pin "3") (pinfunction "3_3") (pintype "passive"))
    )
    (net (code "120") (name "GND") (class "Default")
      (node (ref "C15") (pin "1") (pinfunction "1_1") (pintype "passive"))
      (node (ref "C16") (pin "1") (pinfunction "1_1") (pintype "passive"))
      (node (ref "C17") (pin "1") (pinfunction "1_1") (pintype "passive"))
      (node (ref "C19") (pin "2") (pinfunction "2_2") (pintype "passive"))
      (node (ref "C21") (pin "1") (pinfunction "1_1") (pintype "passive"))
      (node (ref "C22") (pin "1") (pinfunction "1_1") (pintype "passive"))
      (node (ref "C23") (pin "2") (pinfunction "2_2") (pintype "passive"))
      (node (ref "C24") (pin "1") (pinfunction "1_1") (pintype "passive"))
      (node (ref "C25") (pin "1") (pinfunction "1_1") (pintype "passive"))
      (node (ref "C31") (pin "1") (pinfunction "1_1") (pintype "passive"))
      (node (ref "C33") (pin "1") (pinfunction "1_1") (pintype "passive"))
      (node (ref "C34") (pin "2") (pinfunction "2_2") (pintype "passive"))
      (node (ref "C35") (pin "2") (pinfunction "2_2") (pintype "passive"))
      (node (ref "C37") (pin "1") (pinfunction "1_1") (pintype "passive"))
      (node (ref "C38") (pin "1") (pinfunction "1_1") (pintype "passive"))
      (node (ref "C39") (pin "1") (pinfunction "1_1") (pintype "passive"))
      (node (ref "C40") (pin "1") (pinfunction "1_1") (pintype "passive"))
      (node (ref "C41") (pin "1") (pinfunction "1_1") (pintype "passive"))
      (node (ref "J1") (pin "7") (pinfunction "GND_7") (pintype "passive"))
      (node (ref "JP1") (pin "11") (pinfunction "11_11") (pintype "passive"))
      (node (ref "JP1") (pin "12") (pinfunction "12_12") (pintype "passive"))
      (node (ref "JP1") (pin "13") (pinfunction "13_13") (pintype "passive"))
      (node (ref "JP1") (pin "14") (pinfunction "14_14") (pintype "passive"))
      (node (ref "JP1") (pin "59") (pinfunction "59_59") (pintype "passive"))
      (node (ref "JP1") (pin "60") (pinfunction "60_60") (pintype "passive"))
      (node (ref "JP1") (pin "61") (pinfunction "61_61") (pintype "passive"))
      (node (ref "JP1") (pin "62") (pinfunction "62_62") (pintype "passive"))
      (node (ref "JP2") (pin "1") (pinfunction "1_1") (pintype "passive"))
      (node (ref "JP2") (pin "2") (pinfunction "2_2") (pintype "passive"))
      (node (ref "JP4") (pin "20") (pinfunction "20_20") (pintype "passive"))
      (node (ref "Q1") (pin "2") (pinfunction "E_2") (pintype "passive"))
      (node (ref "Q6") (pin "2") (pinfunction "E_2") (pintype "passive"))
      (node (ref "R36") (pin "1") (pinfunction "1_1") (pintype "passive"))
      (node (ref "R57") (pin "1") (pinfunction "1_1") (pintype "passive"))
      (node (ref "R58") (pin "1") (pinfunction "1_1") (pintype "passive"))
      (node (ref "R60") (pin "1") (pinfunction "1_1") (pintype "passive"))
      (node (ref "U1") (pin "11") (pinfunction "Vssa_11") (pintype "passive"))
      (node (ref "U1") (pin "15") (pinfunction "Vss_15") (pintype "passive"))
      (node (ref "U1") (pin "31") (pinfunction "Vss_31") (pintype "passive"))
      (node (ref "U1") (pin "41") (pinfunction "Vss_41") (pintype "passive"))
      (node (ref "U1") (pin "55") (pinfunction "Vss_55") (pintype "passive"))
      (node (ref "U1") (pin "72") (pinfunction "Vss_72") (pintype "passive"))
      (node (ref "U1") (pin "83") (pinfunction "Vss_83") (pintype "passive"))
      (node (ref "U1") (pin "97") (pinfunction "Vss_97") (pintype "passive"))
      (node (ref "U12") (pin "2") (pinfunction "GND_2") (pintype "passive"))
      (node (ref "U12") (pin "8") (pinfunction "S_8") (pintype "passive"))
      (node (ref "U13") (pin "2") (pinfunction "GND_2") (pintype "power_in"))
      (node (ref "U19") (pin "2") (pinfunction "GND_2") (pintype "power_in"))
      (node (ref "U7") (pin "3") (pinfunction "GND_3") (pintype "passive"))
    )
    (net (code "121") (name "Net-(A1-Pad2)") (class "Default")
      (node (ref "A1") (pin "2") (pinfunction "2_2") (pintype "passive"))
      (node (ref "C19") (pin "1") (pinfunction "1_1") (pintype "passive"))
      (node (ref "R56") (pin "1") (pinfunction "1_1") (pintype "passive"))
      (node (ref "R57") (pin "2") (pinfunction "2_2") (pintype "passive"))
    )
    (net (code "122") (name "Net-(C22-Pad2)") (class "Default")
      (node (ref "C22") (pin "2") (pinfunction "2_2") (pintype "passive"))
      (node (ref "K1") (pin "1") (pinfunction "1_1") (pintype "passive"))
      (node (ref "R61") (pin "1") (pinfunction "1_1") (pintype "passive"))
      (node (ref "R64") (pin "1") (pinfunction "1_1") (pintype "passive"))
    )
    (net (code "123") (name "Net-(C23-Pad1)") (class "Default")
      (node (ref "C23") (pin "1") (pinfunction "1_1") (pintype "passive"))
      (node (ref "K1") (pin "3") (pinfunction "3_3") (pintype "passive"))
      (node (ref "R63") (pin "1") (pinfunction "1_1") (pintype "passive"))
      (node (ref "R65") (pin "1") (pinfunction "1_1") (pintype "passive"))
    )
    (net (code "124") (name "Net-(Q1-B)") (class "Default")
      (node (ref "Q1") (pin "1") (pinfunction "B_1") (pintype "passive"))
      (node (ref "R34") (pin "2") (pinfunction "2_2") (pintype "passive"))
      (node (ref "R36") (pin "2") (pinfunction "2_2") (pintype "passive"))
    )
    (net (code "125") (name "Net-(Q1-C)") (class "Default")
      (node (ref "A1") (pin "1") (pinfunction "1_1") (pintype "passive"))
      (node (ref "Q1") (pin "3") (pinfunction "C_3") (pintype "passive"))
    )
    (net (code "126") (name "Net-(Q5-G)") (class "Default")
      (node (ref "JP8") (pin "1") (pinfunction "1_1") (pintype "passive"))
      (node (ref "JP8") (pin "2") (pinfunction "2_2") (pintype "passive"))
      (node (ref "Q5") (pin "1") (pinfunction "G_1") (pintype "passive"))
      (node (ref "U13") (pin "1") (pinfunction "~{RST}_1") (pintype "power_in"))
    )
    (net (code "127") (name "Net-(Q5-S)") (class "Default")
      (node (ref "Q5") (pin "2") (pinfunction "S_2") (pintype "passive"))
      (node (ref "U13") (pin "4") (pinfunction "WDI_4") (pintype "passive"))
    )
    (net (code "128") (name "Net-(Q6-B)") (class "Default")
      (node (ref "Q6") (pin "1") (pinfunction "B_1") (pintype "passive"))
      (node (ref "R35") (pin "2") (pinfunction "2_2") (pintype "passive"))
      (node (ref "R58") (pin "2") (pinfunction "2_2") (pintype "passive"))
    )
    (net (code "129") (name "Net-(Q6-C)") (class "Default")
      (node (ref "K1") (pin "5") (pinfunction "5_5") (pintype "passive"))
      (node (ref "Q6") (pin "3") (pinfunction "C_3") (pintype "passive"))
    )
    (net (code "130") (name "Net-(U7-outA)") (class "Default")
      (node (ref "R40") (pin "2") (pinfunction "2_2") (pintype "passive"))
      (node (ref "U7") (pin "7") (pinfunction "outA_7") (pintype "passive"))
    )
    (net (code "131") (name "Net-(U7-outB)") (class "Default")
      (node (ref "R41") (pin "2") (pinfunction "2_2") (pintype "passive"))
      (node (ref "U7") (pin "5") (pinfunction "outB_5") (pintype "passive"))
    )
    (net (code "132") (name "Net-(U9-IN+)") (class "Default")
      (node (ref "C35") (pin "1") (pinfunction "1_1") (pintype "passive"))
      (node (ref "R60") (pin "2") (pinfunction "2_2") (pintype "passive"))
      (node (ref "R65") (pin "2") (pinfunction "2_2") (pintype "passive"))
      (node (ref "U9") (pin "3") (pinfunction "IN+_3") (pintype "input"))
    )
    (net (code "133") (name "Net-(U9-IN-)") (class "Default")
      (node (ref "C32") (pin "1") (pinfunction "1_1") (pintype "passive"))
      (node (ref "R59") (pin "2") (pinfunction "2_2") (pintype "passive"))
      (node (ref "R64") (pin "2") (pinfunction "2_2") (pintype "passive"))
      (node (ref "U9") (pin "2") (pinfunction "IN-_2") (pintype "input"))
    )
    (net (code "134") (name "Net-(U9-OUT)") (class "Default")
      (node (ref "C24") (pin "2") (pinfunction "2_2") (pintype "passive"))
      (node (ref "C32") (pin "2") (pinfunction "2_2") (pintype "passive"))
      (node (ref "R59") (pin "1") (pinfunction "1_1") (pintype "passive"))
      (node (ref "R66") (pin "1") (pinfunction "1_1") (pintype "passive"))
      (node (ref "U9") (pin "6") (pinfunction "OUT_6") (pintype "output"))
    )
    (net (code "135") (name "unconnected-(JP1-Pad3)") (class "Default")
      (node (ref "JP1") (pin "3") (pinfunction "3_3") (pintype "passive"))
    )
    (net (code "136") (name "unconnected-(JP1-Pad4)") (class "Default")
      (node (ref "JP1") (pin "4") (pinfunction "4_4") (pintype "passive"))
    )
    (net (code "137") (name "unconnected-(JP1-Pad15)") (class "Default")
      (node (ref "JP1") (pin "15") (pinfunction "15_15") (pintype "passive"))
    )
    (net (code "138") (name "unconnected-(JP1-Pad16)") (class "Default")
      (node (ref "JP1") (pin "16") (pinfunction "16_16") (pintype "passive"))
    )
    (net (code "139") (name "unconnected-(JP1-Pad29)") (class "Default")
      (node (ref "JP1") (pin "29") (pinfunction "29_29") (pintype "passive"))
    )
    (net (code "140") (name "unconnected-(JP1-Pad30)") (class "Default")
      (node (ref "JP1") (pin "30") (pinfunction "30_30") (pintype "passive"))
    )
    (net (code "141") (name "unconnected-(JP1-Pad31)") (class "Default")
      (node (ref "JP1") (pin "31") (pinfunction "31_31") (pintype "passive"))
    )
    (net (code "142") (name "unconnected-(JP1-Pad32)") (class "Default")
      (node (ref "JP1") (pin "32") (pinfunction "32_32") (pintype "passive"))
    )
    (net (code "143") (name "unconnected-(JP1-Pad42)") (class "Default")
      (node (ref "JP1") (pin "42") (pinfunction "42_42") (pintype "passive"))
    )
    (net (code "144") (name "unconnected-(JP4-Pad13)") (class "Default")
      (node (ref "JP4") (pin "13") (pinfunction "13_13") (pintype "passive"))
    )
    (net (code "145") (name "unconnected-(JP4-Pad14)") (class "Default")
      (node (ref "JP4") (pin "14") (pinfunction "14_14") (pintype "passive"))
    )
    (net (code "146") (name "unconnected-(JP4-Pad15)") (class "Default")
      (node (ref "JP4") (pin "15") (pinfunction "15_15") (pintype "passive"))
    )
    (net (code "147") (name "unconnected-(JP4-Pad16)") (class "Default")
      (node (ref "JP4") (pin "16") (pinfunction "16_16") (pintype "passive"))
    )
    (net (code "148") (name "unconnected-(JP4-Pad17)") (class "Default")
      (node (ref "JP4") (pin "17") (pinfunction "17_17") (pintype "passive"))
    )
    (net (code "149") (name "unconnected-(K1-Pad2)") (class "Default")
      (node (ref "K1") (pin "2") (pinfunction "2_2") (pintype "passive"))
    )
    (net (code "150") (name "unconnected-(U1-RTCK-Pad100)") (class "Default")
      (node (ref "U1") (pin "100") (pinfunction "RTCK_100") (pintype "passive"))
    )
    (net (code "151") (name "unconnected-(U1-TCK-Pad5)") (class "Default")
      (node (ref "U1") (pin "5") (pinfunction "TCK_5") (pintype "passive"))
    )
    (net (code "152") (name "unconnected-(U1-TDI-Pad2)") (class "Default")
      (node (ref "U1") (pin "2") (pinfunction "TDI_2") (pintype "passive"))
    )
    (net (code "153") (name "unconnected-(U1-TDO-Pad1)") (class "Default")
      (node (ref "U1") (pin "1") (pinfunction "TDO_1") (pintype "passive"))
    )
    (net (code "154") (name "unconnected-(U1-TMS-Pad3)") (class "Default")
      (node (ref "U1") (pin "3") (pinfunction "TMS_3") (pintype "passive"))
    )
    (net (code "155") (name "unconnected-(U1-~{RSTOUT}-Pad14)") (class "Default")
      (node (ref "U1") (pin "14") (pinfunction "~{RSTOUT}_14") (pintype "passive"))
    )
    (net (code "156") (name "unconnected-(U1-~{TRST}-Pad4)") (class "Default")
      (node (ref "U1") (pin "4") (pinfunction "~{TRST}_4") (pintype "passive"))
    )
    (net (code "157") (name "unconnected-(U9-NC-Pad5)") (class "Default")
      (node (ref "U9") (pin "5") (pinfunction "NC_5") (pintype "passive"))
    )
    (net (code "158") (name "unconnected-(U9-VOSTRIM-Pad1)") (class "Default")
      (node (ref "U9") (pin "1") (pinfunction "VOSTRIM_1") (pintype "passive"))
    )
    (net (code "159") (name "unconnected-(U9-VOSTRIM-Pad8)") (class "Default")
      (node (ref "U9") (pin "8") (pinfunction "VOSTRIM_8") (pintype "passive"))
    )
    (net (code "160") (name "unconnected-(U12-Vref-Pad5)") (class "Default")
      (node (ref "U12") (pin "5") (pinfunction "Vref_5") (pintype "passive"))
    )
    (net (code "161") (name "unconnected-(U19-NC-Pad4)") (class "Default")
      (node (ref "U19") (pin "4") (pinfunction "NC_4") (pintype "passive"))
    )
  )
)
